# opamp.net
KiCad netlist of a schematic drawn in Altium Designer
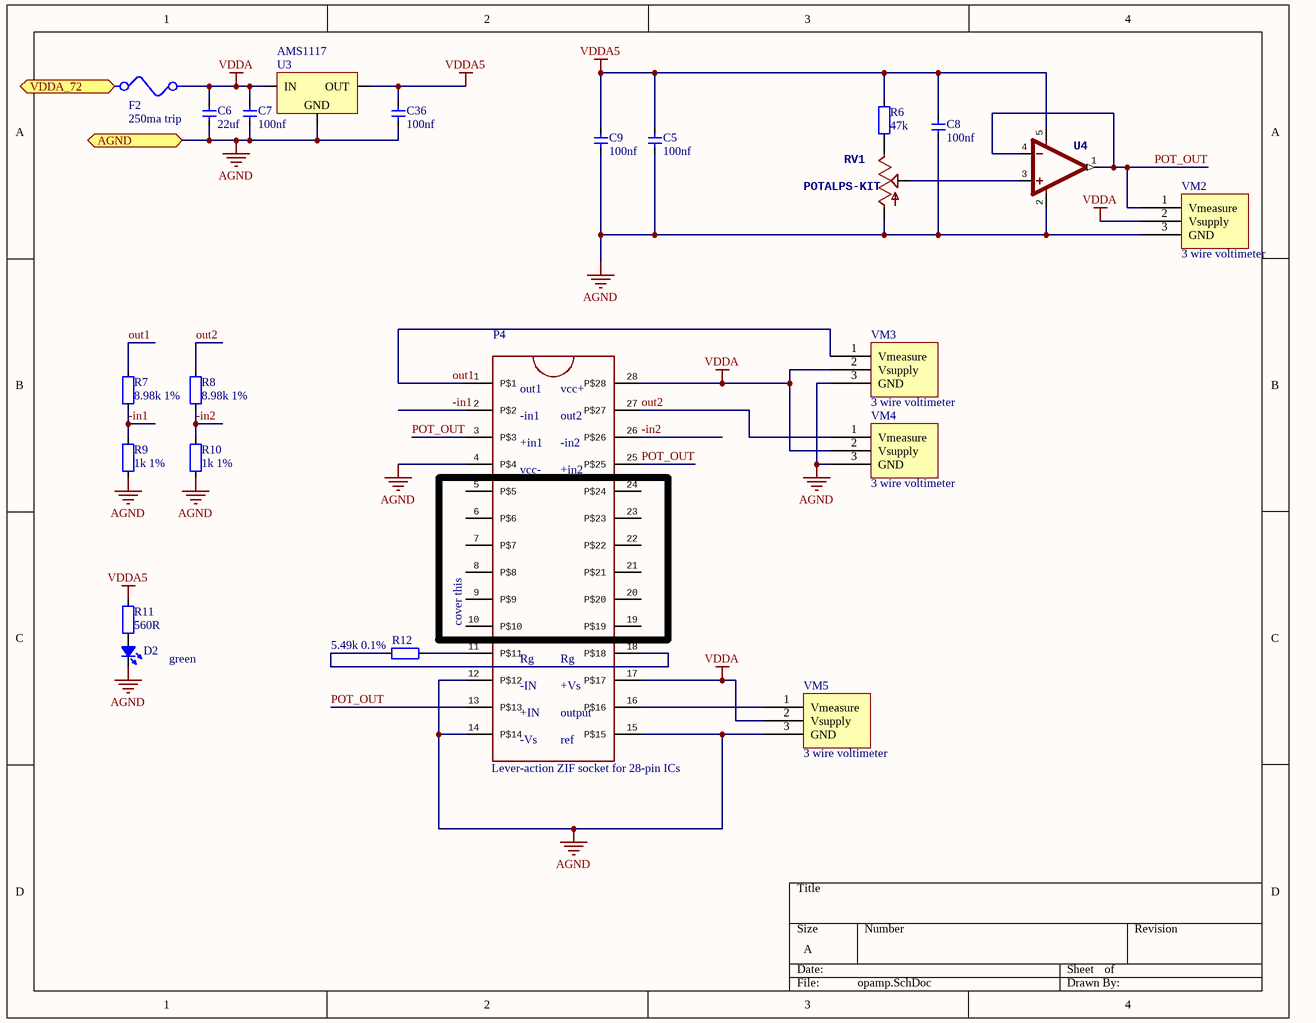
[diagram p0: opamp.SchDoc]

(export (version "E")
  (design (tool "Eeschema 10.0.6"))
  (components
    (comp (ref "C5")
      (value "100nf")
      (footprint "PCB_PassiveCap:CAP_0805")
      (description "Capacitor")
      (fields (field (name "Comment") "Cap_0805"))
      (libsource (lib "SCH_Passive") (part "Cap_0805"))
    )
    (comp (ref "C6")
      (value "22uf")
      (footprint "PCB_PassiveCap:CAP_0805")
      (description "Capacitor")
      (fields (field (name "Comment") "Cap_0805"))
      (libsource (lib "SCH_Passive") (part "Cap_0805"))
    )
    (comp (ref "C7")
      (value "100nf")
      (footprint "PCB_PassiveCap:CAP_0805")
      (description "Capacitor")
      (fields (field (name "Comment") "Cap_0805"))
      (libsource (lib "SCH_Passive") (part "Cap_0805"))
    )
    (comp (ref "C8")
      (value "100nf")
      (footprint "PCB_PassiveCap:CAP_0805")
      (description "Capacitor")
      (fields (field (name "Comment") "Cap_0805"))
      (libsource (lib "SCH_Passive") (part "Cap_0805"))
    )
    (comp (ref "C9")
      (value "100nf")
      (footprint "PCB_PassiveCap:CAP_0805")
      (description "Capacitor")
      (fields (field (name "Comment") "Cap_0805"))
      (libsource (lib "SCH_Passive") (part "Cap_0805"))
    )
    (comp (ref "C36")
      (value "100nf")
      (footprint "PCB_PassiveCap:CAP_0805")
      (description "Capacitor")
      (fields (field (name "Comment") "Cap_0805"))
      (libsource (lib "SCH_Passive") (part "Cap_0805"))
    )
    (comp (ref "D2")
      (value "LED_0805")
      (footprint "PCB_ActiveLED:LED_0805_RED")
      (description "LED")
      (libsource (lib "SCH_Active") (part "LED_0805"))
    )
    (comp (ref "F2")
      (value "250ma trip")
      (footprint "Multifuse1812")
      (description "RO ZEK MULTI 500MA SMD 1812 MF-MSMF050-2 BOURNS")
      (fields (field (name "MFG") "BOURNS"))
      (libsource (lib "Ultimaker") (part "Multifuse"))
    )
    (comp (ref "P4")
      (value "Lever-action ZIF socket for 28-pin ICs")
      (footprint "DIL28-3-ZIF_SOCKET")
      (libsource (lib "SparkFun-Connectors") (part "ZIFSOCKET-28-3ZIFFSOCKET-28-3"))
    )
    (comp (ref "R6")
      (value "47k")
      (footprint "PCB_PassiveRes:RES_0805")
      (description "Resistor")
      (fields (field (name "Comment") "Res_0805"))
      (libsource (lib "") (part "Res_0805_1"))
    )
    (comp (ref "R7")
      (value "8.98k 1%")
      (footprint "PCB_PassiveRes:RES_0805")
      (description "Resistor")
      (fields (field (name "Comment") "Res_0805"))
      (libsource (lib "") (part "Res_0805_1"))
    )
    (comp (ref "R8")
      (value "8.98k 1%")
      (footprint "PCB_PassiveRes:RES_0805")
      (description "Resistor")
      (fields (field (name "Comment") "Res_0805"))
      (libsource (lib "") (part "Res_0805_1"))
    )
    (comp (ref "R9")
      (value "1k 1%")
      (footprint "PCB_PassiveRes:RES_0805")
      (description "Resistor")
      (fields (field (name "Comment") "Res_0805"))
      (libsource (lib "SCH_Passive") (part "Res_0805"))
    )
    (comp (ref "R10")
      (value "1k 1%")
      (footprint "PCB_PassiveRes:RES_0805")
      (description "Resistor")
      (fields (field (name "Comment") "Res_0805"))
      (libsource (lib "SCH_Passive") (part "Res_0805"))
    )
    (comp (ref "R11")
      (value "560R")
      (footprint "PCB_PassiveRes:RES_0805")
      (description "Resistor")
      (fields (field (name "Comment") "Res_0805"))
      (libsource (lib "SCH_Passive") (part "Res_0805"))
    )
    (comp (ref "R12")
      (value "5.49k 0.1%")
      (footprint "PCB_PassiveRes:RES_0805")
      (description "Resistor")
      (fields (field (name "Comment") "Res_0805"))
      (libsource (lib "") (part "Res_0805_2"))
    )
    (comp (ref "RV1")
      (value "POTALPS-KIT")
      (footprint "Bourns-slimline-axialbracket")
      (libsource (lib "SparkFun-Electromechanical") (part "POTALPS-KIT"))
    )
    (comp (ref "U3")
      (value "AMS1117")
      (footprint "SOT223-3-CONNECTEDTAB")
      (description "Power")
      (libsource (lib "SCH_IntegratedCircuit") (part "AMS1117"))
    )
    (comp (ref "U4")
      (value "Rail to rail OpAmp with 10MHz GBP")
      (footprint "SOT23-5")
      (libsource (lib "SparkFun-AnalogIC") (part "MCP6291T-E/OT"))
    )
    (comp (ref "VM2")
      (value "3 wire voltimeter")
      (footprint "led_meter_0.36")
      (libsource (lib "Schlib1") (part "Voltmeter_LED_3wire"))
    )
    (comp (ref "VM3")
      (value "3 wire voltimeter")
      (footprint "led_meter_0.36")
      (libsource (lib "Schlib1") (part "Voltmeter_LED_3wire"))
    )
    (comp (ref "VM4")
      (value "3 wire voltimeter")
      (footprint "led_meter_0.36")
      (libsource (lib "Schlib1") (part "Voltmeter_LED_3wire"))
    )
    (comp (ref "VM5")
      (value "3 wire voltimeter")
      (footprint "led_meter_0.36")
      (libsource (lib "Schlib1") (part "Voltmeter_LED_3wire"))
    )
  )
  (nets
    (net (code "1") (name "/-in1") (class "Default")
      (node (ref "P4") (pin "2") (pinfunction "P$2_2") (pintype "passive"))
      (node (ref "R7") (pin "2") (pinfunction "2_2") (pintype "passive"))
      (node (ref "R9") (pin "2") (pinfunction "2_2") (pintype "passive"))
    )
    (net (code "2") (name "/-in2") (class "Default")
      (node (ref "P4") (pin "26") (pinfunction "P$26_26") (pintype "passive"))
      (node (ref "R10") (pin "2") (pinfunction "2_2") (pintype "passive"))
      (node (ref "R8") (pin "2") (pinfunction "2_2") (pintype "passive"))
    )
    (net (code "3") (name "/POT_OUT") (class "Default")
      (node (ref "P4") (pin "13") (pinfunction "P$13_13") (pintype "passive"))
      (node (ref "P4") (pin "25") (pinfunction "P$25_25") (pintype "passive"))
      (node (ref "P4") (pin "3") (pinfunction "P$3_3") (pintype "passive"))
      (node (ref "U4") (pin "1") (pinfunction "OUT_1") (pintype "output"))
      (node (ref "U4") (pin "4") (pinfunction "-IN_4") (pintype "passive"))
      (node (ref "VM2") (pin "1") (pinfunction "Vmeasure_1") (pintype "passive"))
    )
    (net (code "4") (name "/VDDA_72") (class "Default")
      (node (ref "F2") (pin "1") (pinfunction "1_1") (pintype "passive"))
    )
    (net (code "5") (name "/out1") (class "Default")
      (node (ref "P4") (pin "1") (pinfunction "P$1_1") (pintype "passive"))
      (node (ref "R7") (pin "1") (pinfunction "1_1") (pintype "passive"))
      (node (ref "VM3") (pin "1") (pinfunction "Vmeasure_1") (pintype "passive"))
    )
    (net (code "6") (name "/out2") (class "Default")
      (node (ref "P4") (pin "27") (pinfunction "P$27_27") (pintype "passive"))
      (node (ref "R8") (pin "1") (pinfunction "1_1") (pintype "passive"))
      (node (ref "VM4") (pin "1") (pinfunction "Vmeasure_1") (pintype "passive"))
    )
    (net (code "7") (name "AGND") (class "Default")
      (node (ref "C36") (pin "1") (pinfunction "1_1") (pintype "passive"))
      (node (ref "C5") (pin "1") (pinfunction "1_1") (pintype "passive"))
      (node (ref "C6") (pin "1") (pinfunction "1_1") (pintype "passive"))
      (node (ref "C7") (pin "1") (pinfunction "1_1") (pintype "passive"))
      (node (ref "C8") (pin "2") (pinfunction "2_2") (pintype "passive"))
      (node (ref "C9") (pin "1") (pinfunction "1_1") (pintype "passive"))
      (node (ref "D2") (pin "2") (pinfunction "K_2") (pintype "passive"))
      (node (ref "P4") (pin "12") (pinfunction "P$12_12") (pintype "passive"))
      (node (ref "P4") (pin "14") (pinfunction "P$14_14") (pintype "passive"))
      (node (ref "P4") (pin "15") (pinfunction "P$15_15") (pintype "passive"))
      (node (ref "P4") (pin "4") (pinfunction "P$4_4") (pintype "passive"))
      (node (ref "R10") (pin "1") (pinfunction "1_1") (pintype "passive"))
      (node (ref "R9") (pin "1") (pinfunction "1_1") (pintype "passive"))
      (node (ref "RV1") (pin "P$3") (pinfunction "A_P$3") (pintype "passive"))
      (node (ref "U3") (pin "1") (pinfunction "GND_1") (pintype "power_in"))
      (node (ref "U4") (pin "2") (pinfunction "V-_2") (pintype "power_in"))
      (node (ref "VM2") (pin "3") (pinfunction "GND_3") (pintype "passive"))
      (node (ref "VM3") (pin "3") (pinfunction "GND_3") (pintype "passive"))
      (node (ref "VM4") (pin "3") (pinfunction "GND_3") (pintype "passive"))
      (node (ref "VM5") (pin "3") (pinfunction "GND_3") (pintype "passive"))
    )
    (net (code "8") (name "Net-(D2-A)") (class "Default")
      (node (ref "D2") (pin "1") (pinfunction "A_1") (pintype "passive"))
      (node (ref "R11") (pin "1") (pinfunction "1_1") (pintype "passive"))
    )
    (net (code "9") (name "Net-(P4-P$11)") (class "Default")
      (node (ref "P4") (pin "11") (pinfunction "P$11_11") (pintype "passive"))
      (node (ref "R12") (pin "2") (pinfunction "2_2") (pintype "passive"))
    )
    (net (code "10") (name "Net-(P4-P$16)") (class "Default")
      (node (ref "P4") (pin "16") (pinfunction "P$16_16") (pintype "passive"))
      (node (ref "VM5") (pin "1") (pinfunction "Vmeasure_1") (pintype "passive"))
    )
    (net (code "11") (name "Net-(P4-P$18)") (class "Default")
      (node (ref "P4") (pin "18") (pinfunction "P$18_18") (pintype "passive"))
      (node (ref "R12") (pin "1") (pinfunction "1_1") (pintype "passive"))
    )
    (net (code "12") (name "Net-(RV1-E)") (class "Default")
      (node (ref "R6") (pin "2") (pinfunction "2_2") (pintype "passive"))
      (node (ref "RV1") (pin "P$1") (pinfunction "E_P$1") (pintype "passive"))
    )
    (net (code "13") (name "Net-(RV1-S)") (class "Default")
      (node (ref "RV1") (pin "P$2") (pinfunction "S_P$2") (pintype "passive"))
      (node (ref "U4") (pin "3") (pinfunction "+IN_3") (pintype "passive"))
    )
    (net (code "14") (name "VDDA") (class "Default")
      (node (ref "C6") (pin "2") (pinfunction "2_2") (pintype "passive"))
      (node (ref "C7") (pin "2") (pinfunction "2_2") (pintype "passive"))
      (node (ref "F2") (pin "2") (pinfunction "2_2") (pintype "passive"))
      (node (ref "P4") (pin "17") (pinfunction "P$17_17") (pintype "passive"))
      (node (ref "P4") (pin "28") (pinfunction "P$28_28") (pintype "passive"))
      (node (ref "U3") (pin "3") (pinfunction "IN_3") (pintype "power_in"))
      (node (ref "VM2") (pin "2") (pinfunction "Vsupply_2") (pintype "passive"))
      (node (ref "VM3") (pin "2") (pinfunction "Vsupply_2") (pintype "passive"))
      (node (ref "VM4") (pin "2") (pinfunction "Vsupply_2") (pintype "passive"))
      (node (ref "VM5") (pin "2") (pinfunction "Vsupply_2") (pintype "passive"))
    )
    (net (code "15") (name "VDDA5") (class "Default")
      (node (ref "C36") (pin "2") (pinfunction "2_2") (pintype "passive"))
      (node (ref "C5") (pin "2") (pinfunction "2_2") (pintype "passive"))
      (node (ref "C8") (pin "1") (pinfunction "1_1") (pintype "passive"))
      (node (ref "C9") (pin "2") (pinfunction "2_2") (pintype "passive"))
      (node (ref "R11") (pin "2") (pinfunction "2_2") (pintype "passive"))
      (node (ref "R6") (pin "1") (pinfunction "1_1") (pintype "passive"))
      (node (ref "U3") (pin "2") (pinfunction "OUT_2") (pintype "power_in"))
      (node (ref "U4") (pin "5") (pinfunction "V+_5") (pintype "power_in"))
    )
    (net (code "16") (name "unconnected-(P4-P$5-Pad5)") (class "Default")
      (node (ref "P4") (pin "5") (pinfunction "P$5_5") (pintype "passive"))
    )
    (net (code "17") (name "unconnected-(P4-P$6-Pad6)") (class "Default")
      (node (ref "P4") (pin "6") (pinfunction "P$6_6") (pintype "passive"))
    )
    (net (code "18") (name "unconnected-(P4-P$7-Pad7)") (class "Default")
      (node (ref "P4") (pin "7") (pinfunction "P$7_7") (pintype "passive"))
    )
    (net (code "19") (name "unconnected-(P4-P$8-Pad8)") (class "Default")
      (node (ref "P4") (pin "8") (pinfunction "P$8_8") (pintype "passive"))
    )
    (net (code "20") (name "unconnected-(P4-P$9-Pad9)") (class "Default")
      (node (ref "P4") (pin "9") (pinfunction "P$9_9") (pintype "passive"))
    )
    (net (code "21") (name "unconnected-(P4-P$10-Pad10)") (class "Default")
      (node (ref "P4") (pin "10") (pinfunction "P$10_10") (pintype "passive"))
    )
    (net (code "22") (name "unconnected-(P4-P$19-Pad19)") (class "Default")
      (node (ref "P4") (pin "19") (pinfunction "P$19_19") (pintype "passive"))
    )
    (net (code "23") (name "unconnected-(P4-P$20-Pad20)") (class "Default")
      (node (ref "P4") (pin "20") (pinfunction "P$20_20") (pintype "passive"))
    )
    (net (code "24") (name "unconnected-(P4-P$21-Pad21)") (class "Default")
      (node (ref "P4") (pin "21") (pinfunction "P$21_21") (pintype "passive"))
    )
    (net (code "25") (name "unconnected-(P4-P$22-Pad22)") (class "Default")
      (node (ref "P4") (pin "22") (pinfunction "P$22_22") (pintype "passive"))
    )
    (net (code "26") (name "unconnected-(P4-P$23-Pad23)") (class "Default")
      (node (ref "P4") (pin "23") (pinfunction "P$23_23") (pintype "passive"))
    )
    (net (code "27") (name "unconnected-(P4-P$24-Pad24)") (class "Default")
      (node (ref "P4") (pin "24") (pinfunction "P$24_24") (pintype "passive"))
    )
  )
)
